# SCH1_Connectors.net
KiCad netlist of a schematic drawn in Altium Designer
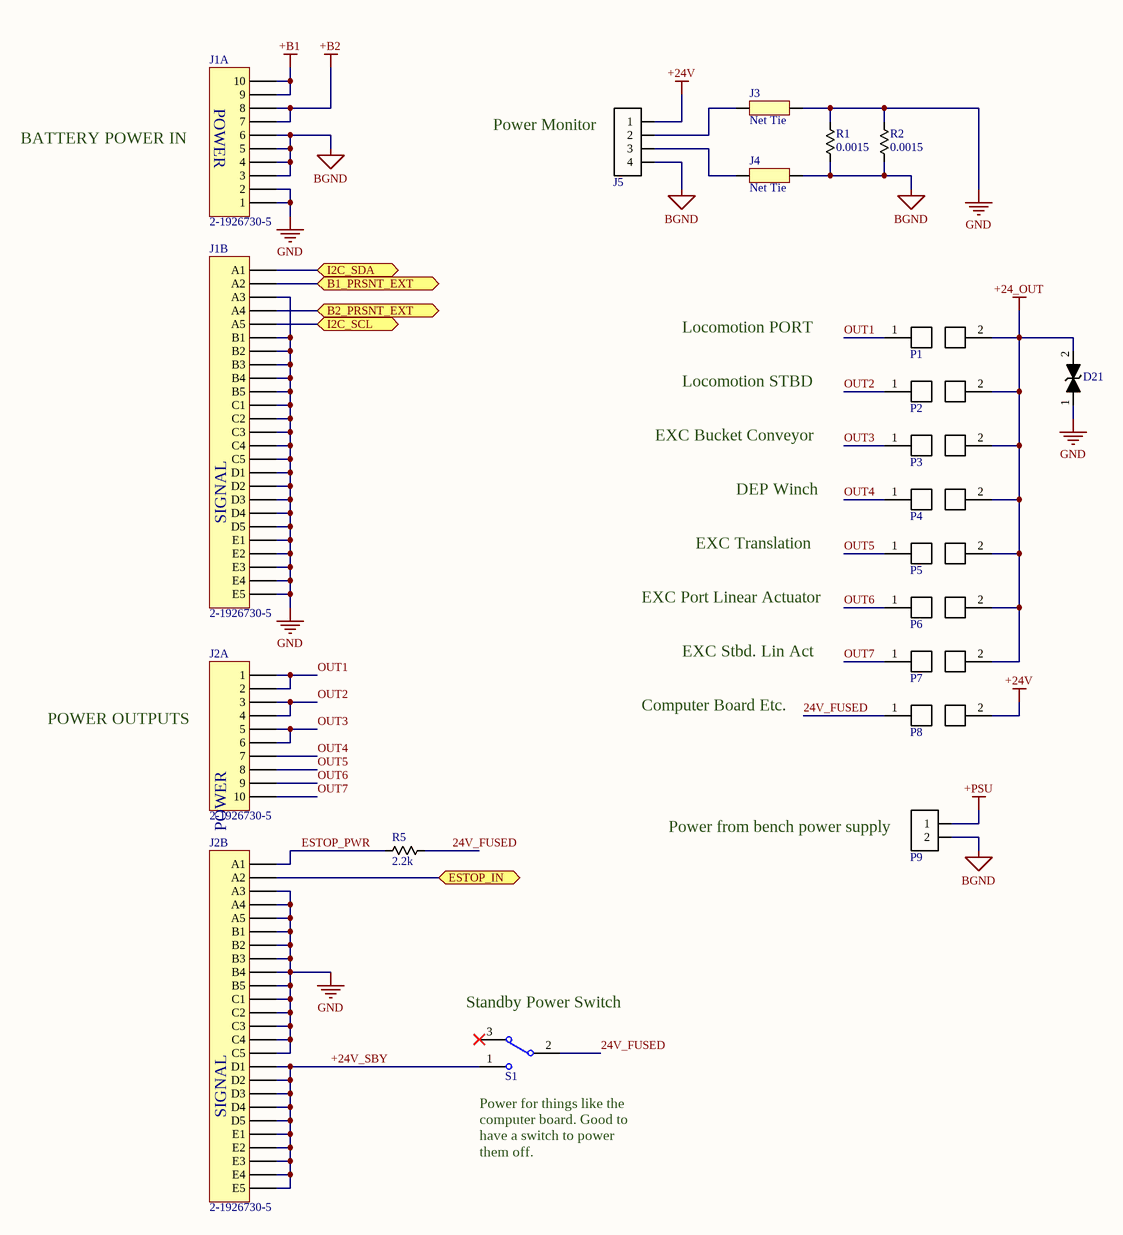
[diagram p0: SCH1_Connectors.SchDoc]

(export (version "E")
  (design (tool "Eeschema 10.0.6"))
  (components
    (comp (ref "D21")
      (value "diode_5")
      (footprint "do-214ab")
      (description "TVS, 28V, 45.5V@66A, 3kW 66A Peak, Bidirectional, DO-214AC")
      (fields (field (name "PART NUMBER") "DIO-00090") (field (name "MANUFACTURER") "ST"))
      (libsource (lib "Diodes$") (part "DIO-00090"))
    )
    (comp (ref "J1")
      (value "2-1926730-5")
      (footprint "TE_CONN_2-1926730-5")
      (description "Backplane Header, Blades and Pins, Edge Mount Right Angle, 10 Power 25 Signal")
      (fields (field (name "PART NUMBER") "CONN-00093") (field (name "MANUFACTURER") "TE Connectivity"))
      (libsource (lib "Connectors$") (part "CONN-00093"))
    )
    (comp (ref "J2")
      (value "2-1926730-5")
      (footprint "TE_CONN_2-1926730-5")
      (description "Backplane Header, Blades and Pins, Edge Mount Right Angle, 10 Power 25 Signal")
      (fields (field (name "PART NUMBER") "CONN-00093") (field (name "MANUFACTURER") "TE Connectivity"))
      (libsource (lib "") (part "CONN-00093_1"))
    )
    (comp (ref "J3")
      (value "Net Tie")
      (footprint "net_tie_0")
      (fields (field (name "PART NUMBER") "MISC-00039"))
      (libsource (lib "Misc$") (part "MISC-00039"))
    )
    (comp (ref "J4")
      (value "Net Tie")
      (footprint "net_tie_0")
      (fields (field (name "PART NUMBER") "MISC-00039"))
      (libsource (lib "Misc$") (part "MISC-00039"))
    )
    (comp (ref "J5")
      (value "conn-4x1_0")
      (footprint "PHOENIX_1757268")
      (description "Terminal Block Header, 4 pos, 12A 300V, Right-Angle, THT")
      (fields (field (name "PART NUMBER") "CONN-00096") (field (name "MANUFACTURER") "Phoenix Contact"))
      (libsource (lib "Connectors$") (part "CONN-00096"))
    )
    (comp (ref "P1")
      (value "conn-fuse-holder_0")
      (footprint "FUSE_HOLDER_KEYSTONE_3557-2")
      (description "Fuse Holder, 30A, 500V, LP-Mini 897, ATOF 257")
      (fields (field (name "PART NUMBER") "CONN-00015") (field (name "MANUFACTURER") "Keystone Electronics"))
      (libsource (lib "Connectors$") (part "CONN-00015"))
    )
    (comp (ref "P2")
      (value "conn-fuse-holder_0")
      (footprint "FUSE_HOLDER_KEYSTONE_3557-2")
      (description "Fuse Holder, 30A, 500V, LP-Mini 897, ATOF 257")
      (fields (field (name "PART NUMBER") "CONN-00015") (field (name "MANUFACTURER") "Keystone Electronics"))
      (libsource (lib "Connectors$") (part "CONN-00015"))
    )
    (comp (ref "P3")
      (value "conn-fuse-holder_0")
      (footprint "FUSE_HOLDER_KEYSTONE_3557-2")
      (description "Fuse Holder, 30A, 500V, LP-Mini 897, ATOF 257")
      (fields (field (name "PART NUMBER") "CONN-00015") (field (name "MANUFACTURER") "Keystone Electronics"))
      (libsource (lib "Connectors$") (part "CONN-00015"))
    )
    (comp (ref "P4")
      (value "conn-fuse-holder_0")
      (footprint "FUSE_HOLDER_KEYSTONE_3557-2")
      (description "Fuse Holder, 30A, 500V, LP-Mini 897, ATOF 257")
      (fields (field (name "PART NUMBER") "CONN-00015") (field (name "MANUFACTURER") "Keystone Electronics"))
      (libsource (lib "Connectors$") (part "CONN-00015"))
    )
    (comp (ref "P5")
      (value "conn-fuse-holder_0")
      (footprint "FUSE_HOLDER_KEYSTONE_3557-2")
      (description "Fuse Holder, 30A, 500V, LP-Mini 897, ATOF 257")
      (fields (field (name "PART NUMBER") "CONN-00015") (field (name "MANUFACTURER") "Keystone Electronics"))
      (libsource (lib "Connectors$") (part "CONN-00015"))
    )
    (comp (ref "P6")
      (value "conn-fuse-holder_0")
      (footprint "FUSE_HOLDER_KEYSTONE_3557-2")
      (description "Fuse Holder, 30A, 500V, LP-Mini 897, ATOF 257")
      (fields (field (name "PART NUMBER") "CONN-00015") (field (name "MANUFACTURER") "Keystone Electronics"))
      (libsource (lib "Connectors$") (part "CONN-00015"))
    )
    (comp (ref "P7")
      (value "conn-fuse-holder_0")
      (footprint "FUSE_HOLDER_KEYSTONE_3557-2")
      (description "Fuse Holder, 30A, 500V, LP-Mini 897, ATOF 257")
      (fields (field (name "PART NUMBER") "CONN-00015") (field (name "MANUFACTURER") "Keystone Electronics"))
      (libsource (lib "Connectors$") (part "CONN-00015"))
    )
    (comp (ref "P8")
      (value "conn-fuse-holder_0")
      (footprint "FUSE_HOLDER_KEYSTONE_3557-2")
      (description "Fuse Holder, 30A, 500V, LP-Mini 897, ATOF 257")
      (fields (field (name "PART NUMBER") "CONN-00015") (field (name "MANUFACTURER") "Keystone Electronics"))
      (libsource (lib "Connectors$") (part "CONN-00015"))
    )
    (comp (ref "P9")
      (value "conn-2x1_0")
      (footprint "PHOENIX_1757242")
      (description "Terminal Blk Header, 2 Pos, 5.08mm, 12A, Right-Angle")
      (fields (field (name "PART NUMBER") "CONN-00102") (field (name "MANUFACTURER") "Phoenix Contact"))
      (libsource (lib "Connectors$") (part "CONN-00102"))
    )
    (comp (ref "R1")
      (value "0.0015")
      (footprint "chip_2512")
      (description "RES SMD 0.0015 OHM 1% 3W 2512 50ppm, Current Sense")
      (fields (field (name "PART NUMBER") "RES-00716") (field (name "TOLERANCE") "1%"))
      (libsource (lib "Resistors$") (part "RES-00716"))
    )
    (comp (ref "R2")
      (value "0.0015")
      (footprint "chip_2512")
      (description "RES SMD 0.0015 OHM 1% 3W 2512 50ppm, Current Sense")
      (fields (field (name "PART NUMBER") "RES-00716") (field (name "TOLERANCE") "1%"))
      (libsource (lib "Resistors$") (part "RES-00716"))
    )
    (comp (ref "R5")
      (value "2.2k")
      (footprint "chip_0805")
      (description "RES SMD 2.2K OHM 1% 1/8W 0805")
      (fields (field (name "PART NUMBER") "RES-00366") (field (name "TOLERANCE") "1%"))
      (libsource (lib "Resistors$") (part "RES-00366"))
    )
    (comp (ref "S1")
      (value "SW-SPDT")
      (footprint "M2012TXG41-DC")
      (description "Switch, SPDT, Rocker, Thru-hole, Right-angle")
      (fields (field (name "PART NUMBER") "MISC-00009") (field (name "MANUFACTURER") "NKK Switches"))
      (libsource (lib "Misc$") (part "MISC-00009"))
    )
  )
  (nets
    (net (code "1") (name "+24V") (class "Default")
      (node (ref "J5") (pin "1") (pinfunction "1_1") (pintype "passive"))
      (node (ref "P8") (pin "2") (pinfunction "2_2") (pintype "passive"))
    )
    (net (code "2") (name "+24_OUT") (class "Default")
      (node (ref "D21") (pin "2") (pinfunction "2_2") (pintype "passive"))
      (node (ref "P1") (pin "2") (pinfunction "2_2") (pintype "passive"))
      (node (ref "P2") (pin "2") (pinfunction "2_2") (pintype "passive"))
      (node (ref "P3") (pin "2") (pinfunction "2_2") (pintype "passive"))
      (node (ref "P4") (pin "2") (pinfunction "2_2") (pintype "passive"))
      (node (ref "P5") (pin "2") (pinfunction "2_2") (pintype "passive"))
      (node (ref "P6") (pin "2") (pinfunction "2_2") (pintype "passive"))
      (node (ref "P7") (pin "2") (pinfunction "2_2") (pintype "passive"))
    )
    (net (code "3") (name "+B1") (class "Default")
      (node (ref "J1") (pin "10") (pinfunction "10_10") (pintype "passive"))
      (node (ref "J1") (pin "9") (pinfunction "9_9") (pintype "passive"))
    )
    (net (code "4") (name "+B2") (class "Default")
      (node (ref "J1") (pin "7") (pinfunction "7_7") (pintype "passive"))
      (node (ref "J1") (pin "8") (pinfunction "8_8") (pintype "passive"))
    )
    (net (code "5") (name "+PSU") (class "Default")
      (node (ref "P9") (pin "1") (pinfunction "1_1") (pintype "passive"))
    )
    (net (code "6") (name "/+24V_SBY") (class "Default")
      (node (ref "J2") (pin "D1") (pinfunction "D1_D1") (pintype "passive"))
      (node (ref "J2") (pin "D2") (pinfunction "D2_D2") (pintype "passive"))
      (node (ref "J2") (pin "D3") (pinfunction "D3_D3") (pintype "passive"))
      (node (ref "J2") (pin "D4") (pinfunction "D4_D4") (pintype "passive"))
      (node (ref "J2") (pin "D5") (pinfunction "D5_D5") (pintype "passive"))
      (node (ref "J2") (pin "E1") (pinfunction "E1_E1") (pintype "passive"))
      (node (ref "J2") (pin "E2") (pinfunction "E2_E2") (pintype "passive"))
      (node (ref "J2") (pin "E3") (pinfunction "E3_E3") (pintype "passive"))
      (node (ref "J2") (pin "E4") (pinfunction "E4_E4") (pintype "passive"))
      (node (ref "J2") (pin "E5") (pinfunction "E5_E5") (pintype "passive"))
      (node (ref "S1") (pin "1") (pinfunction "1_1") (pintype "passive"))
    )
    (net (code "7") (name "/24V_FUSED") (class "Default")
      (node (ref "P8") (pin "1") (pinfunction "1_1") (pintype "passive"))
      (node (ref "R5") (pin "2") (pinfunction "2_2") (pintype "passive"))
      (node (ref "S1") (pin "2") (pinfunction "2_2") (pintype "passive"))
    )
    (net (code "8") (name "/B1_PRSNT_EXT") (class "Default")
      (node (ref "J1") (pin "A2") (pinfunction "A2_A2") (pintype "passive"))
    )
    (net (code "9") (name "/B2_PRSNT_EXT") (class "Default")
      (node (ref "J1") (pin "A4") (pinfunction "A4_A4") (pintype "passive"))
    )
    (net (code "10") (name "/ESTOP_IN") (class "Default")
      (node (ref "J2") (pin "A2") (pinfunction "A2_A2") (pintype "passive"))
    )
    (net (code "11") (name "/ESTOP_PWR") (class "Default")
      (node (ref "J2") (pin "A1") (pinfunction "A1_A1") (pintype "passive"))
      (node (ref "R5") (pin "1") (pinfunction "1_1") (pintype "passive"))
    )
    (net (code "12") (name "/I2C_SCL") (class "Default")
      (node (ref "J1") (pin "A5") (pinfunction "A5_A5") (pintype "passive"))
    )
    (net (code "13") (name "/I2C_SDA") (class "Default")
      (node (ref "J1") (pin "A1") (pinfunction "A1_A1") (pintype "passive"))
    )
    (net (code "14") (name "/OUT1") (class "Default")
      (node (ref "J2") (pin "1") (pinfunction "1_1") (pintype "passive"))
      (node (ref "J2") (pin "2") (pinfunction "2_2") (pintype "passive"))
      (node (ref "P1") (pin "1") (pinfunction "1_1") (pintype "passive"))
    )
    (net (code "15") (name "/OUT2") (class "Default")
      (node (ref "J2") (pin "3") (pinfunction "3_3") (pintype "passive"))
      (node (ref "J2") (pin "4") (pinfunction "4_4") (pintype "passive"))
      (node (ref "P2") (pin "1") (pinfunction "1_1") (pintype "passive"))
    )
    (net (code "16") (name "/OUT3") (class "Default")
      (node (ref "J2") (pin "5") (pinfunction "5_5") (pintype "passive"))
      (node (ref "J2") (pin "6") (pinfunction "6_6") (pintype "passive"))
      (node (ref "P3") (pin "1") (pinfunction "1_1") (pintype "passive"))
    )
    (net (code "17") (name "/OUT4") (class "Default")
      (node (ref "J2") (pin "7") (pinfunction "7_7") (pintype "passive"))
      (node (ref "P4") (pin "1") (pinfunction "1_1") (pintype "passive"))
    )
    (net (code "18") (name "/OUT5") (class "Default")
      (node (ref "J2") (pin "8") (pinfunction "8_8") (pintype "passive"))
      (node (ref "P5") (pin "1") (pinfunction "1_1") (pintype "passive"))
    )
    (net (code "19") (name "/OUT6") (class "Default")
      (node (ref "J2") (pin "9") (pinfunction "9_9") (pintype "passive"))
      (node (ref "P6") (pin "1") (pinfunction "1_1") (pintype "passive"))
    )
    (net (code "20") (name "/OUT7") (class "Default")
      (node (ref "J2") (pin "10") (pinfunction "10_10") (pintype "passive"))
      (node (ref "P7") (pin "1") (pinfunction "1_1") (pintype "passive"))
    )
    (net (code "21") (name "BGND") (class "Default")
      (node (ref "J1") (pin "3") (pinfunction "3_3") (pintype "passive"))
      (node (ref "J1") (pin "4") (pinfunction "4_4") (pintype "passive"))
      (node (ref "J1") (pin "5") (pinfunction "5_5") (pintype "passive"))
      (node (ref "J1") (pin "6") (pinfunction "6_6") (pintype "passive"))
      (node (ref "J4") (pin "2") (pinfunction "NET2_2") (pintype "power_in"))
      (node (ref "J5") (pin "4") (pinfunction "4_4") (pintype "passive"))
      (node (ref "P9") (pin "2") (pinfunction "2_2") (pintype "passive"))
      (node (ref "R1") (pin "2") (pinfunction "2_2") (pintype "passive"))
      (node (ref "R2") (pin "2") (pinfunction "2_2") (pintype "passive"))
    )
    (net (code "22") (name "GND") (class "Default")
      (node (ref "D21") (pin "1") (pinfunction "1_1") (pintype "passive"))
      (node (ref "J1") (pin "1") (pinfunction "1_1") (pintype "passive"))
      (node (ref "J1") (pin "2") (pinfunction "2_2") (pintype "passive"))
      (node (ref "J1") (pin "A3") (pinfunction "A3_A3") (pintype "passive"))
      (node (ref "J1") (pin "B1") (pinfunction "B1_B1") (pintype "passive"))
      (node (ref "J1") (pin "B2") (pinfunction "B2_B2") (pintype "passive"))
      (node (ref "J1") (pin "B3") (pinfunction "B3_B3") (pintype "passive"))
      (node (ref "J1") (pin "B4") (pinfunction "B4_B4") (pintype "passive"))
      (node (ref "J1") (pin "B5") (pinfunction "B5_B5") (pintype "passive"))
      (node (ref "J1") (pin "C1") (pinfunction "C1_C1") (pintype "passive"))
      (node (ref "J1") (pin "C2") (pinfunction "C2_C2") (pintype "passive"))
      (node (ref "J1") (pin "C3") (pinfunction "C3_C3") (pintype "passive"))
      (node (ref "J1") (pin "C4") (pinfunction "C4_C4") (pintype "passive"))
      (node (ref "J1") (pin "C5") (pinfunction "C5_C5") (pintype "passive"))
      (node (ref "J1") (pin "D1") (pinfunction "D1_D1") (pintype "passive"))
      (node (ref "J1") (pin "D2") (pinfunction "D2_D2") (pintype "passive"))
      (node (ref "J1") (pin "D3") (pinfunction "D3_D3") (pintype "passive"))
      (node (ref "J1") (pin "D4") (pinfunction "D4_D4") (pintype "passive"))
      (node (ref "J1") (pin "D5") (pinfunction "D5_D5") (pintype "passive"))
      (node (ref "J1") (pin "E1") (pinfunction "E1_E1") (pintype "passive"))
      (node (ref "J1") (pin "E2") (pinfunction "E2_E2") (pintype "passive"))
      (node (ref "J1") (pin "E3") (pinfunction "E3_E3") (pintype "passive"))
      (node (ref "J1") (pin "E4") (pinfunction "E4_E4") (pintype "passive"))
      (node (ref "J1") (pin "E5") (pinfunction "E5_E5") (pintype "passive"))
      (node (ref "J2") (pin "A3") (pinfunction "A3_A3") (pintype "passive"))
      (node (ref "J2") (pin "A4") (pinfunction "A4_A4") (pintype "passive"))
      (node (ref "J2") (pin "A5") (pinfunction "A5_A5") (pintype "passive"))
      (node (ref "J2") (pin "B1") (pinfunction "B1_B1") (pintype "passive"))
      (node (ref "J2") (pin "B2") (pinfunction "B2_B2") (pintype "passive"))
      (node (ref "J2") (pin "B3") (pinfunction "B3_B3") (pintype "passive"))
      (node (ref "J2") (pin "B4") (pinfunction "B4_B4") (pintype "passive"))
      (node (ref "J2") (pin "B5") (pinfunction "B5_B5") (pintype "passive"))
      (node (ref "J2") (pin "C1") (pinfunction "C1_C1") (pintype "passive"))
      (node (ref "J2") (pin "C2") (pinfunction "C2_C2") (pintype "passive"))
      (node (ref "J2") (pin "C3") (pinfunction "C3_C3") (pintype "passive"))
      (node (ref "J2") (pin "C4") (pinfunction "C4_C4") (pintype "passive"))
      (node (ref "J2") (pin "C5") (pinfunction "C5_C5") (pintype "passive"))
      (node (ref "J3") (pin "2") (pinfunction "NET2_2") (pintype "power_in"))
      (node (ref "R1") (pin "1") (pinfunction "1_1") (pintype "passive"))
      (node (ref "R2") (pin "1") (pinfunction "1_1") (pintype "passive"))
    )
    (net (code "23") (name "Net-(J3-NET1)") (class "Default")
      (node (ref "J3") (pin "1") (pinfunction "NET1_1") (pintype "power_in"))
      (node (ref "J5") (pin "2") (pinfunction "2_2") (pintype "passive"))
    )
    (net (code "24") (name "Net-(J4-NET1)") (class "Default")
      (node (ref "J4") (pin "1") (pinfunction "NET1_1") (pintype "power_in"))
      (node (ref "J5") (pin "3") (pinfunction "3_3") (pintype "passive"))
    )
    (net (code "25") (name "unconnected-(S1-Pad3)") (class "Default")
      (node (ref "S1") (pin "3") (pinfunction "3_3") (pintype "passive+no_connect"))
    )
  )
)
